# 02-UART.net
KiCad netlist of a schematic drawn in Altium Designer
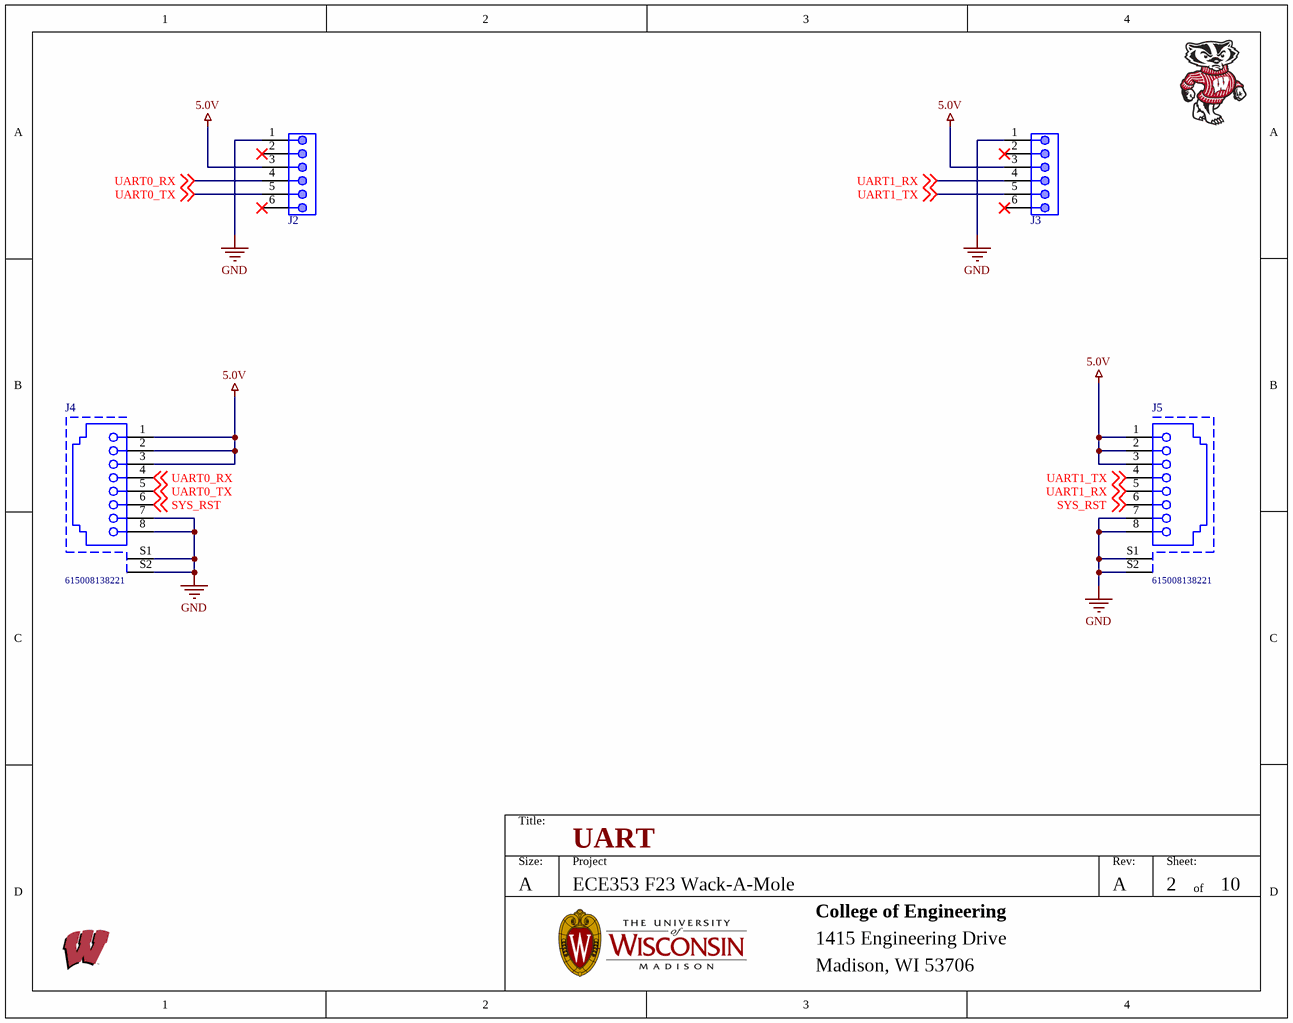
[diagram p0: 02-UART.SchDoc]

(export (version "E")
  (design (tool "Eeschema 10.0.6"))
  (components
    (comp (ref "J2")
      (value "~")
      (footprint "HDR1X6")
      (description "Female, 6C, Rt Angle, .100\"CC; 3.15mm Tail, No Mounting; PBT, Phos. Bronze, 105 C")
      (libsource (lib "Connectors") (part "CONN_HEADER_MALE_1x6"))
    )
    (comp (ref "J3")
      (value "~")
      (footprint "HDR1X6")
      (description "Female, 6C, Rt Angle, .100\"CC; 3.15mm Tail, No Mounting; PBT, Phos. Bronze, 105 C")
      (libsource (lib "Connectors") (part "CONN_HEADER_MALE_1x6"))
    )
    (comp (ref "J4")
      (value "615008138221")
      (footprint "615008138221")
      (description "Modular Jack WR-MJ, Front Post, Shielded, Vertical Entry, THT, 8P8C")
      (fields (field (name "MANUFACTURER") "Wurth Elektronik") (field (name "PUBLISHER") "WurthElektronik"))
      (libsource (lib "Altium Content Vault") (part "WE-CN-1P-2F-J8"))
    )
    (comp (ref "J5")
      (value "615008138221")
      (footprint "615008138221")
      (description "Modular Jack WR-MJ, Front Post, Shielded, Vertical Entry, THT, 8P8C")
      (fields (field (name "MANUFACTURER") "Wurth Elektronik") (field (name "PUBLISHER") "WurthElektronik"))
      (libsource (lib "Altium Content Vault") (part "WE-CN-1P-2F-J8"))
    )
  )
  (nets
    (net (code "1") (name "5.0V") (class "Default")
      (node (ref "J2") (pin "3") (pinfunction "3_3") (pintype "passive"))
      (node (ref "J3") (pin "3") (pinfunction "3_3") (pintype "passive"))
      (node (ref "J4") (pin "1") (pinfunction "1_1") (pintype "passive"))
      (node (ref "J4") (pin "2") (pinfunction "2_2") (pintype "passive"))
      (node (ref "J4") (pin "3") (pinfunction "3_3") (pintype "passive"))
      (node (ref "J5") (pin "1") (pinfunction "1_1") (pintype "passive"))
      (node (ref "J5") (pin "2") (pinfunction "2_2") (pintype "passive"))
      (node (ref "J5") (pin "3") (pinfunction "3_3") (pintype "passive"))
    )
    (net (code "2") (name "GND") (class "Default")
      (node (ref "J2") (pin "1") (pinfunction "1_1") (pintype "passive"))
      (node (ref "J3") (pin "1") (pinfunction "1_1") (pintype "passive"))
      (node (ref "J4") (pin "7") (pinfunction "7_7") (pintype "passive"))
      (node (ref "J4") (pin "8") (pinfunction "8_8") (pintype "passive"))
      (node (ref "J4") (pin "S1") (pinfunction "S1_S1") (pintype "passive"))
      (node (ref "J4") (pin "S2") (pinfunction "S2_S2") (pintype "passive"))
      (node (ref "J5") (pin "7") (pinfunction "7_7") (pintype "passive"))
      (node (ref "J5") (pin "8") (pinfunction "8_8") (pintype "passive"))
      (node (ref "J5") (pin "S1") (pinfunction "S1_S1") (pintype "passive"))
      (node (ref "J5") (pin "S2") (pinfunction "S2_S2") (pintype "passive"))
    )
    (net (code "3") (name "SYS_RST") (class "Default")
      (node (ref "J4") (pin "6") (pinfunction "6_6") (pintype "passive"))
      (node (ref "J5") (pin "6") (pinfunction "6_6") (pintype "passive"))
    )
    (net (code "4") (name "UART0_RX") (class "Default")
      (node (ref "J2") (pin "4") (pinfunction "4_4") (pintype "passive"))
      (node (ref "J4") (pin "4") (pinfunction "4_4") (pintype "passive"))
    )
    (net (code "5") (name "UART0_TX") (class "Default")
      (node (ref "J2") (pin "5") (pinfunction "5_5") (pintype "passive"))
      (node (ref "J4") (pin "5") (pinfunction "5_5") (pintype "passive"))
    )
    (net (code "6") (name "UART1_RX") (class "Default")
      (node (ref "J3") (pin "4") (pinfunction "4_4") (pintype "passive"))
      (node (ref "J5") (pin "5") (pinfunction "5_5") (pintype "passive"))
    )
    (net (code "7") (name "UART1_TX") (class "Default")
      (node (ref "J3") (pin "5") (pinfunction "5_5") (pintype "passive"))
      (node (ref "J5") (pin "4") (pinfunction "4_4") (pintype "passive"))
    )
    (net (code "8") (name "unconnected-(J2-Pad2)") (class "Default")
      (node (ref "J2") (pin "2") (pinfunction "2_2") (pintype "passive+no_connect"))
    )
    (net (code "9") (name "unconnected-(J2-Pad6)") (class "Default")
      (node (ref "J2") (pin "6") (pinfunction "6_6") (pintype "passive+no_connect"))
    )
    (net (code "10") (name "unconnected-(J3-Pad2)") (class "Default")
      (node (ref "J3") (pin "2") (pinfunction "2_2") (pintype "passive+no_connect"))
    )
    (net (code "11") (name "unconnected-(J3-Pad6)") (class "Default")
      (node (ref "J3") (pin "6") (pinfunction "6_6") (pintype "passive+no_connect"))
    )
  )
)
